# Dev_BRD_STM32F103C8T6.net
KiCad netlist of a schematic drawn in Altium Designer
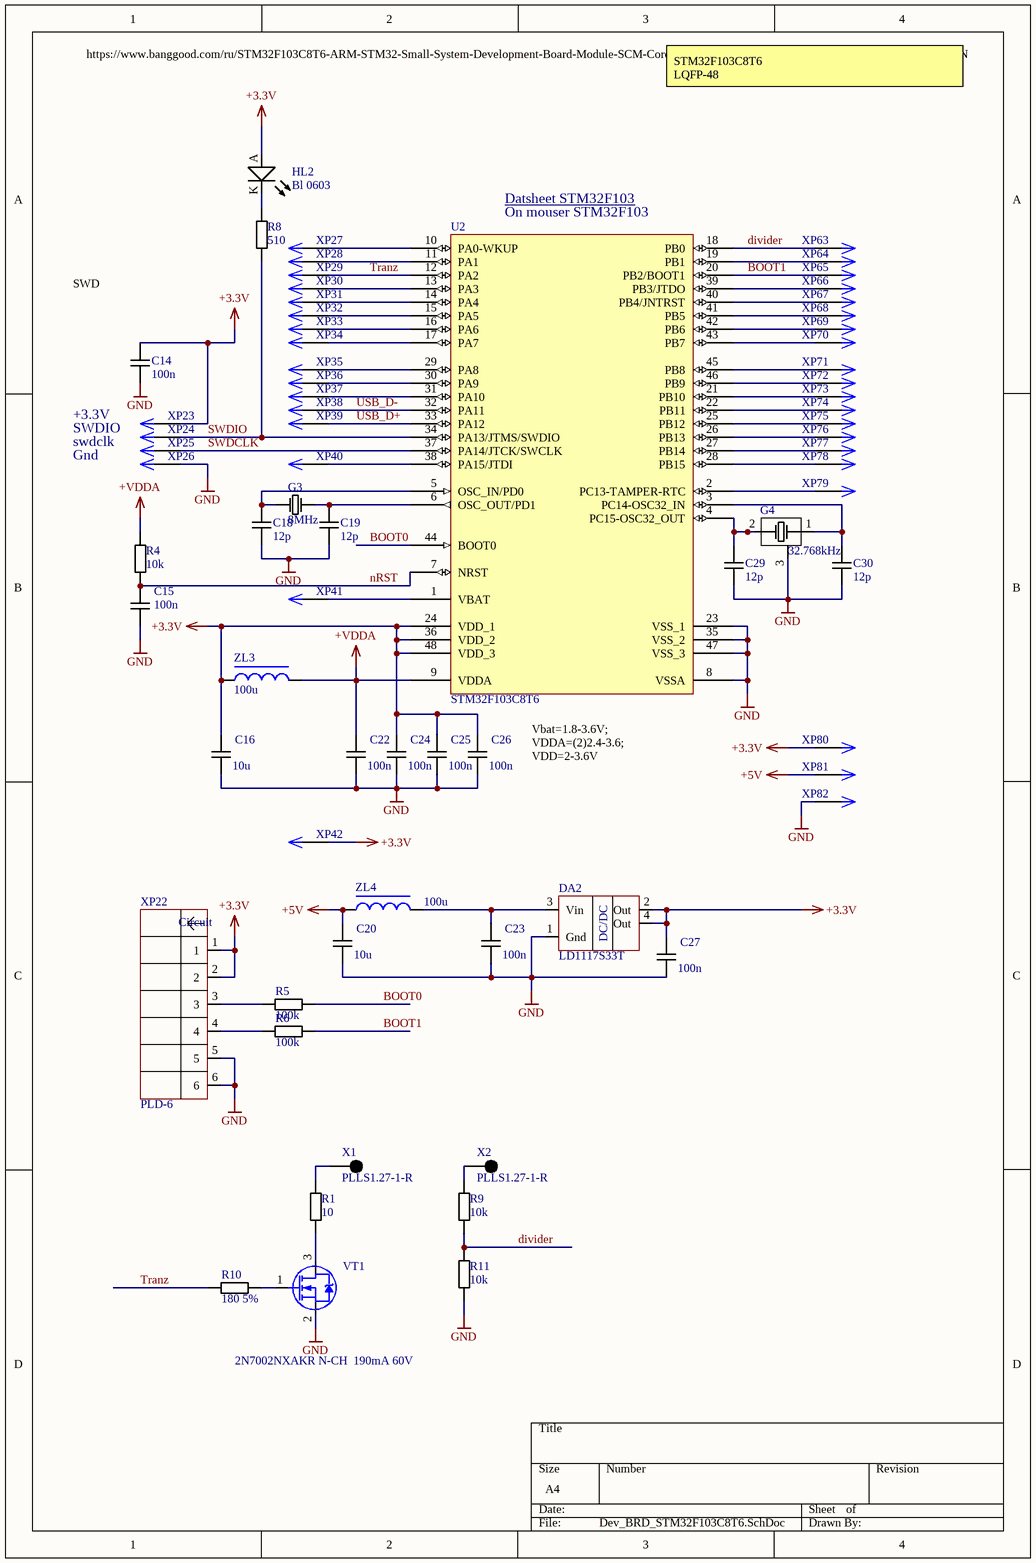
[diagram p0: Dev_BRD_STM32F103C8T6.SchDoc]

(export (version "E")
  (design (tool "Eeschema 10.0.6"))
  (components
    (comp (ref "C14")
      (value "100n")
      (footprint "CAPC1608(0603)N")
      (description "?")
      (fields (field (name "PART NUMBER") "CAPC1608(0603)"))
      (libsource (lib "SssAccesDatbase") (part "Cap"))
    )
    (comp (ref "C15")
      (value "100n")
      (footprint "CAPC1608(0603)N")
      (description "?")
      (fields (field (name "PART NUMBER") "CAPC1608(0603)"))
      (libsource (lib "SssAccesDatbase") (part "Cap"))
    )
    (comp (ref "C16")
      (value "10u")
      (footprint "CAPC1608(0603)N")
      (description "?")
      (fields (field (name "PART NUMBER") "CAPC1608(0603)"))
      (libsource (lib "SssAccesDatbase") (part "Cap"))
    )
    (comp (ref "C18")
      (value "12p")
      (footprint "CAPC1608(0603)N")
      (description "?")
      (fields (field (name "PART NUMBER") "CAPC1608(0603)"))
      (libsource (lib "SssAccesDatbase") (part "Cap"))
    )
    (comp (ref "C19")
      (value "12p")
      (footprint "CAPC1608(0603)N")
      (description "?")
      (fields (field (name "PART NUMBER") "CAPC1608(0603)"))
      (libsource (lib "SssAccesDatbase") (part "Cap"))
    )
    (comp (ref "C20")
      (value "10u")
      (footprint "CAPC1608(0603)N")
      (description "?")
      (fields (field (name "PART NUMBER") "CAPC1608(0603)"))
      (libsource (lib "SssAccesDatbase") (part "Cap"))
    )
    (comp (ref "C22")
      (value "100n")
      (footprint "CAPC1608(0603)N")
      (description "?")
      (fields (field (name "PART NUMBER") "CAPC1608(0603)"))
      (libsource (lib "SssAccesDatbase") (part "Cap"))
    )
    (comp (ref "C23")
      (value "100n")
      (footprint "CAPC1608(0603)N")
      (description "?")
      (fields (field (name "PART NUMBER") "CAPC1608(0603)"))
      (libsource (lib "SssAccesDatbase") (part "Cap"))
    )
    (comp (ref "C24")
      (value "100n")
      (footprint "CAPC1608(0603)N")
      (description "?")
      (fields (field (name "PART NUMBER") "CAPC1608(0603)"))
      (libsource (lib "SssAccesDatbase") (part "Cap"))
    )
    (comp (ref "C25")
      (value "100n")
      (footprint "CAPC1608(0603)N")
      (description "?")
      (fields (field (name "PART NUMBER") "CAPC1608(0603)"))
      (libsource (lib "SssAccesDatbase") (part "Cap"))
    )
    (comp (ref "C26")
      (value "100n")
      (footprint "CAPC1608(0603)N")
      (description "?")
      (fields (field (name "PART NUMBER") "CAPC1608(0603)"))
      (libsource (lib "SssAccesDatbase") (part "Cap"))
    )
    (comp (ref "C27")
      (value "100n")
      (footprint "CAPC1608(0603)N")
      (description "?")
      (fields (field (name "PART NUMBER") "CAPC1608(0603)"))
      (libsource (lib "SssAccesDatbase") (part "Cap"))
    )
    (comp (ref "C29")
      (value "12p")
      (footprint "CAPC1608(0603)N")
      (description "?")
      (fields (field (name "PART NUMBER") "CAPC1608(0603)"))
      (libsource (lib "SssAccesDatbase") (part "Cap"))
    )
    (comp (ref "C30")
      (value "12p")
      (footprint "CAPC1608(0603)N")
      (description "?")
      (fields (field (name "PART NUMBER") "CAPC1608(0603)"))
      (libsource (lib "SssAccesDatbase") (part "Cap"))
    )
    (comp (ref "DA2")
      (value "LD1117S33T")
      (footprint "SOT223_M")
      (description "LDO Voltage Regulators 3.3V 0.8A Positive")
      (fields (field (name "DIGI-KEY PART NUMBER") "?"))
      (libsource (lib "SssAccesDatbase") (part "LD1117S33T"))
    )
    (comp (ref "G3")
      (value "8MHz")
      (footprint "HC-49/S")
      (description "Crystal HC-49/S")
      (libsource (lib "SssAccesDatbase") (part "Crystal"))
    )
    (comp (ref "G4")
      (value "32.768kHz")
      (footprint "CRYSTAL_CMR309T")
      (description "Crystals 32.768KHz")
      (fields
        (field (name "PART NUMBER") "AB26T-32.768KHZ")
        (field (name "MOUSER PART NUMBER") "815-AB26T-32.768KHZ")
      )
      (libsource (lib "SssAccesDatbase") (part "Crystal 3 pin"))
    )
    (comp (ref "HL2")
      (value "Bl 0603")
      (footprint "LED-0603-BLUE")
      (description "LED BLUE DIFFUSED 0603 SMD")
      (fields
        (field (name "PART NUMBER") "150060BS55040")
        (field (name "DIGI-KEY PART NUMBER") "732-12013-1-ND")
      )
      (libsource (lib "SssAccesDatbase") (part "LED"))
    )
    (comp (ref "R1")
      (value "10")
      (footprint "REZKemet 0402")
      (description "RES SMD 0402 180 5% 100ppm")
      (fields
        (field (name "PART NUMBER") "RMCF0402JT180R")
        (field (name "DIGI-KEY PART NUMBER") "RMCF0402JT180RCT-ND")
      )
      (libsource (lib "SssAccesDatbase") (part "Resistor general"))
    )
    (comp (ref "R4")
      (value "10k")
      (footprint "RESC1608(0603)N")
      (fields (field (name "PART NUMBER") "RESC1608(0603)") (field (name "DIGI-KEY PART NUMBER") "???"))
      (libsource (lib "SssAccesDatbase") (part "Resistor general"))
    )
    (comp (ref "R5")
      (value "100k")
      (footprint "RESC1608(0603)N")
      (fields (field (name "PART NUMBER") "RESC1608(0603)") (field (name "DIGI-KEY PART NUMBER") "???"))
      (libsource (lib "") (part "Resistor general_1"))
    )
    (comp (ref "R6")
      (value "100k")
      (footprint "RESC1608(0603)N")
      (fields (field (name "PART NUMBER") "RESC1608(0603)") (field (name "DIGI-KEY PART NUMBER") "???"))
      (libsource (lib "") (part "Resistor general_1"))
    )
    (comp (ref "R8")
      (value "510")
      (footprint "RESC1608(0603)N")
      (fields (field (name "PART NUMBER") "RESC1608(0603)") (field (name "DIGI-KEY PART NUMBER") "???"))
      (libsource (lib "") (part "Resistor general_2"))
    )
    (comp (ref "R9")
      (value "10k")
      (footprint "RESC1608(0603)N")
      (fields (field (name "PART NUMBER") "RESC1608(0603)") (field (name "DIGI-KEY PART NUMBER") "???"))
      (libsource (lib "SssAccesDatbase") (part "Resistor general"))
    )
    (comp (ref "R10")
      (value "180 5%")
      (footprint "REZKemet 0402")
      (description "RES SMD 0402 180 5% 100ppm")
      (fields
        (field (name "PART NUMBER") "RMCF0402JT180R")
        (field (name "DIGI-KEY PART NUMBER") "RMCF0402JT180RCT-ND")
      )
      (libsource (lib "") (part "Resistor general_3"))
    )
    (comp (ref "R11")
      (value "10k")
      (footprint "RESC1608(0603)N")
      (fields (field (name "PART NUMBER") "RESC1608(0603)") (field (name "DIGI-KEY PART NUMBER") "???"))
      (libsource (lib "SssAccesDatbase") (part "Resistor general"))
    )
    (comp (ref "U2")
      (value "STM32F103C8T6")
      (footprint "LQFP48_L")
      (description "ARM Microcontrollers - MCU 32BIT Cortex M3 64KB 20KB RAM 2X12 ADC")
      (fields
        (field (name "MOUSER PART NUMBER") "511-STM32F103C8T6")
        (field (name "PUBLISHER") "Altium Limited")
      )
      (libsource (lib "SssAccesDatbase") (part "STM32F103C8T6"))
    )
    (comp (ref "VT1")
      (value "2N7002NXAKR N-CH  190mА 60V")
      (footprint "SOT23-3N")
      (description "N-Channel 60V 190mA (Ta), 300mA (Tc) 265mW (Ta), 1.33W (Tc) Surface Mount TO-236AB")
      (fields
        (field (name "PART NUMBER") "2N7002NXAKR")
        (field (name "DIGI-KEY PART NUMBER") "1727-8643-1-ND")
      )
      (libsource (lib "SssAccesDatbase") (part "N-CH_MOSFET_GSD"))
    )
    (comp (ref "X1")
      (value "PLLS1.27-1-R")
      (footprint "PLLS1.27-1-R")
      (libsource (lib "SssAccesDatbase") (part "X1_1"))
    )
    (comp (ref "X2")
      (value "PLLS1.27-1-R")
      (footprint "PLLS1.27-1-R")
      (libsource (lib "SssAccesDatbase") (part "X1_1"))
    )
    (comp (ref "XP22")
      (value "PLD-6")
      (footprint "PLD-6-3D")
      (libsource (lib "SssAccesDatbase") (part "XP-6"))
    )
    (comp (ref "XP23")
      (value "PLS-1")
      (footprint "PLS-1-3D")
      (description "CONN HEADER VERT 1POS")
      (fields
        (field (name "DIGI-KEY PART NUMBER") "S1011EC-01-ND")
        (field (name "MANUFACTURER PART NUMBER") "PRPC001SAAN-RC")
      )
      (libsource (lib "SssAccesDatbase") (part "XP-1_1"))
    )
    (comp (ref "XP24")
      (value "PLS-1")
      (footprint "PLS-1-3D")
      (description "CONN HEADER VERT 1POS")
      (fields
        (field (name "DIGI-KEY PART NUMBER") "S1011EC-01-ND")
        (field (name "MANUFACTURER PART NUMBER") "PRPC001SAAN-RC")
      )
      (libsource (lib "SssAccesDatbase") (part "XP-1_1"))
    )
    (comp (ref "XP25")
      (value "PLS-1")
      (footprint "PLS-1-3D")
      (description "CONN HEADER VERT 1POS")
      (fields
        (field (name "DIGI-KEY PART NUMBER") "S1011EC-01-ND")
        (field (name "MANUFACTURER PART NUMBER") "PRPC001SAAN-RC")
      )
      (libsource (lib "SssAccesDatbase") (part "XP-1_1"))
    )
    (comp (ref "XP26")
      (value "PLS-1")
      (footprint "PLS-1-3D")
      (description "CONN HEADER VERT 1POS")
      (fields
        (field (name "DIGI-KEY PART NUMBER") "S1011EC-01-ND")
        (field (name "MANUFACTURER PART NUMBER") "PRPC001SAAN-RC")
      )
      (libsource (lib "SssAccesDatbase") (part "XP-1_1"))
    )
    (comp (ref "XP27")
      (value "PLS-1")
      (footprint "PLS-1-3D")
      (description "CONN HEADER VERT 1POS")
      (fields
        (field (name "DIGI-KEY PART NUMBER") "S1011EC-01-ND")
        (field (name "MANUFACTURER PART NUMBER") "PRPC001SAAN-RC")
      )
      (libsource (lib "SssAccesDatbase") (part "XP-1_1"))
    )
    (comp (ref "XP28")
      (value "PLS-1")
      (footprint "PLS-1-3D")
      (description "CONN HEADER VERT 1POS")
      (fields
        (field (name "DIGI-KEY PART NUMBER") "S1011EC-01-ND")
        (field (name "MANUFACTURER PART NUMBER") "PRPC001SAAN-RC")
      )
      (libsource (lib "SssAccesDatbase") (part "XP-1_1"))
    )
    (comp (ref "XP29")
      (value "PLS-1")
      (footprint "PLS-1-3D")
      (description "CONN HEADER VERT 1POS")
      (fields
        (field (name "DIGI-KEY PART NUMBER") "S1011EC-01-ND")
        (field (name "MANUFACTURER PART NUMBER") "PRPC001SAAN-RC")
      )
      (libsource (lib "SssAccesDatbase") (part "XP-1_1"))
    )
    (comp (ref "XP30")
      (value "PLS-1")
      (footprint "PLS-1-3D")
      (description "CONN HEADER VERT 1POS")
      (fields
        (field (name "DIGI-KEY PART NUMBER") "S1011EC-01-ND")
        (field (name "MANUFACTURER PART NUMBER") "PRPC001SAAN-RC")
      )
      (libsource (lib "SssAccesDatbase") (part "XP-1_1"))
    )
    (comp (ref "XP31")
      (value "PLS-1")
      (footprint "PLS-1-3D")
      (description "CONN HEADER VERT 1POS")
      (fields
        (field (name "DIGI-KEY PART NUMBER") "S1011EC-01-ND")
        (field (name "MANUFACTURER PART NUMBER") "PRPC001SAAN-RC")
      )
      (libsource (lib "SssAccesDatbase") (part "XP-1_1"))
    )
    (comp (ref "XP32")
      (value "PLS-1")
      (footprint "PLS-1-3D")
      (description "CONN HEADER VERT 1POS")
      (fields
        (field (name "DIGI-KEY PART NUMBER") "S1011EC-01-ND")
        (field (name "MANUFACTURER PART NUMBER") "PRPC001SAAN-RC")
      )
      (libsource (lib "SssAccesDatbase") (part "XP-1_1"))
    )
    (comp (ref "XP33")
      (value "PLS-1")
      (footprint "PLS-1-3D")
      (description "CONN HEADER VERT 1POS")
      (fields
        (field (name "DIGI-KEY PART NUMBER") "S1011EC-01-ND")
        (field (name "MANUFACTURER PART NUMBER") "PRPC001SAAN-RC")
      )
      (libsource (lib "SssAccesDatbase") (part "XP-1_1"))
    )
    (comp (ref "XP34")
      (value "PLS-1")
      (footprint "PLS-1-3D")
      (description "CONN HEADER VERT 1POS")
      (fields
        (field (name "DIGI-KEY PART NUMBER") "S1011EC-01-ND")
        (field (name "MANUFACTURER PART NUMBER") "PRPC001SAAN-RC")
      )
      (libsource (lib "SssAccesDatbase") (part "XP-1_1"))
    )
    (comp (ref "XP35")
      (value "PLS-1")
      (footprint "PLS-1-3D")
      (description "CONN HEADER VERT 1POS")
      (fields
        (field (name "DIGI-KEY PART NUMBER") "S1011EC-01-ND")
        (field (name "MANUFACTURER PART NUMBER") "PRPC001SAAN-RC")
      )
      (libsource (lib "SssAccesDatbase") (part "XP-1_1"))
    )
    (comp (ref "XP36")
      (value "PLS-1")
      (footprint "PLS-1-3D")
      (description "CONN HEADER VERT 1POS")
      (fields
        (field (name "DIGI-KEY PART NUMBER") "S1011EC-01-ND")
        (field (name "MANUFACTURER PART NUMBER") "PRPC001SAAN-RC")
      )
      (libsource (lib "SssAccesDatbase") (part "XP-1_1"))
    )
    (comp (ref "XP37")
      (value "PLS-1")
      (footprint "PLS-1-3D")
      (description "CONN HEADER VERT 1POS")
      (fields
        (field (name "DIGI-KEY PART NUMBER") "S1011EC-01-ND")
        (field (name "MANUFACTURER PART NUMBER") "PRPC001SAAN-RC")
      )
      (libsource (lib "SssAccesDatbase") (part "XP-1_1"))
    )
    (comp (ref "XP38")
      (value "PLS-1")
      (footprint "PLS-1-3D")
      (description "CONN HEADER VERT 1POS")
      (fields
        (field (name "DIGI-KEY PART NUMBER") "S1011EC-01-ND")
        (field (name "MANUFACTURER PART NUMBER") "PRPC001SAAN-RC")
      )
      (libsource (lib "SssAccesDatbase") (part "XP-1_1"))
    )
    (comp (ref "XP39")
      (value "PLS-1")
      (footprint "PLS-1-3D")
      (description "CONN HEADER VERT 1POS")
      (fields
        (field (name "DIGI-KEY PART NUMBER") "S1011EC-01-ND")
        (field (name "MANUFACTURER PART NUMBER") "PRPC001SAAN-RC")
      )
      (libsource (lib "SssAccesDatbase") (part "XP-1_1"))
    )
    (comp (ref "XP40")
      (value "PLS-1")
      (footprint "PLS-1-3D")
      (description "CONN HEADER VERT 1POS")
      (fields
        (field (name "DIGI-KEY PART NUMBER") "S1011EC-01-ND")
        (field (name "MANUFACTURER PART NUMBER") "PRPC001SAAN-RC")
      )
      (libsource (lib "SssAccesDatbase") (part "XP-1_1"))
    )
    (comp (ref "XP41")
      (value "PLS-1")
      (footprint "PLS-1-3D")
      (description "CONN HEADER VERT 1POS")
      (fields
        (field (name "DIGI-KEY PART NUMBER") "S1011EC-01-ND")
        (field (name "MANUFACTURER PART NUMBER") "PRPC001SAAN-RC")
      )
      (libsource (lib "SssAccesDatbase") (part "XP-1_1"))
    )
    (comp (ref "XP42")
      (value "PLS-1")
      (footprint "PLS-1-3D")
      (description "CONN HEADER VERT 1POS")
      (fields
        (field (name "DIGI-KEY PART NUMBER") "S1011EC-01-ND")
        (field (name "MANUFACTURER PART NUMBER") "PRPC001SAAN-RC")
      )
      (libsource (lib "SssAccesDatbase") (part "XP-1_1"))
    )
    (comp (ref "XP63")
      (value "PLS-1")
      (footprint "PLS-1-3D")
      (description "CONN HEADER VERT 1POS")
      (fields
        (field (name "DIGI-KEY PART NUMBER") "S1011EC-01-ND")
        (field (name "MANUFACTURER PART NUMBER") "PRPC001SAAN-RC")
      )
      (libsource (lib "SssAccesDatbase") (part "XP-1_1"))
    )
    (comp (ref "XP64")
      (value "PLS-1")
      (footprint "PLS-1-3D")
      (description "CONN HEADER VERT 1POS")
      (fields
        (field (name "DIGI-KEY PART NUMBER") "S1011EC-01-ND")
        (field (name "MANUFACTURER PART NUMBER") "PRPC001SAAN-RC")
      )
      (libsource (lib "SssAccesDatbase") (part "XP-1_1"))
    )
    (comp (ref "XP65")
      (value "PLS-1")
      (footprint "PLS-1-3D")
      (description "CONN HEADER VERT 1POS")
      (fields
        (field (name "DIGI-KEY PART NUMBER") "S1011EC-01-ND")
        (field (name "MANUFACTURER PART NUMBER") "PRPC001SAAN-RC")
      )
      (libsource (lib "SssAccesDatbase") (part "XP-1_1"))
    )
    (comp (ref "XP66")
      (value "PLS-1")
      (footprint "PLS-1-3D")
      (description "CONN HEADER VERT 1POS")
      (fields
        (field (name "DIGI-KEY PART NUMBER") "S1011EC-01-ND")
        (field (name "MANUFACTURER PART NUMBER") "PRPC001SAAN-RC")
      )
      (libsource (lib "SssAccesDatbase") (part "XP-1_1"))
    )
    (comp (ref "XP67")
      (value "PLS-1")
      (footprint "PLS-1-3D")
      (description "CONN HEADER VERT 1POS")
      (fields
        (field (name "DIGI-KEY PART NUMBER") "S1011EC-01-ND")
        (field (name "MANUFACTURER PART NUMBER") "PRPC001SAAN-RC")
      )
      (libsource (lib "SssAccesDatbase") (part "XP-1_1"))
    )
    (comp (ref "XP68")
      (value "PLS-1")
      (footprint "PLS-1-3D")
      (description "CONN HEADER VERT 1POS")
      (fields
        (field (name "DIGI-KEY PART NUMBER") "S1011EC-01-ND")
        (field (name "MANUFACTURER PART NUMBER") "PRPC001SAAN-RC")
      )
      (libsource (lib "SssAccesDatbase") (part "XP-1_1"))
    )
    (comp (ref "XP69")
      (value "PLS-1")
      (footprint "PLS-1-3D")
      (description "CONN HEADER VERT 1POS")
      (fields
        (field (name "DIGI-KEY PART NUMBER") "S1011EC-01-ND")
        (field (name "MANUFACTURER PART NUMBER") "PRPC001SAAN-RC")
      )
      (libsource (lib "SssAccesDatbase") (part "XP-1_1"))
    )
    (comp (ref "XP70")
      (value "PLS-1")
      (footprint "PLS-1-3D")
      (description "CONN HEADER VERT 1POS")
      (fields
        (field (name "DIGI-KEY PART NUMBER") "S1011EC-01-ND")
        (field (name "MANUFACTURER PART NUMBER") "PRPC001SAAN-RC")
      )
      (libsource (lib "SssAccesDatbase") (part "XP-1_1"))
    )
    (comp (ref "XP71")
      (value "PLS-1")
      (footprint "PLS-1-3D")
      (description "CONN HEADER VERT 1POS")
      (fields
        (field (name "DIGI-KEY PART NUMBER") "S1011EC-01-ND")
        (field (name "MANUFACTURER PART NUMBER") "PRPC001SAAN-RC")
      )
      (libsource (lib "SssAccesDatbase") (part "XP-1_1"))
    )
    (comp (ref "XP72")
      (value "PLS-1")
      (footprint "PLS-1-3D")
      (description "CONN HEADER VERT 1POS")
      (fields
        (field (name "DIGI-KEY PART NUMBER") "S1011EC-01-ND")
        (field (name "MANUFACTURER PART NUMBER") "PRPC001SAAN-RC")
      )
      (libsource (lib "SssAccesDatbase") (part "XP-1_1"))
    )
    (comp (ref "XP73")
      (value "PLS-1")
      (footprint "PLS-1-3D")
      (description "CONN HEADER VERT 1POS")
      (fields
        (field (name "DIGI-KEY PART NUMBER") "S1011EC-01-ND")
        (field (name "MANUFACTURER PART NUMBER") "PRPC001SAAN-RC")
      )
      (libsource (lib "SssAccesDatbase") (part "XP-1_1"))
    )
    (comp (ref "XP74")
      (value "PLS-1")
      (footprint "PLS-1-3D")
      (description "CONN HEADER VERT 1POS")
      (fields
        (field (name "DIGI-KEY PART NUMBER") "S1011EC-01-ND")
        (field (name "MANUFACTURER PART NUMBER") "PRPC001SAAN-RC")
      )
      (libsource (lib "SssAccesDatbase") (part "XP-1_1"))
    )
    (comp (ref "XP75")
      (value "PLS-1")
      (footprint "PLS-1-3D")
      (description "CONN HEADER VERT 1POS")
      (fields
        (field (name "DIGI-KEY PART NUMBER") "S1011EC-01-ND")
        (field (name "MANUFACTURER PART NUMBER") "PRPC001SAAN-RC")
      )
      (libsource (lib "SssAccesDatbase") (part "XP-1_1"))
    )
    (comp (ref "XP76")
      (value "PLS-1")
      (footprint "PLS-1-3D")
      (description "CONN HEADER VERT 1POS")
      (fields
        (field (name "DIGI-KEY PART NUMBER") "S1011EC-01-ND")
        (field (name "MANUFACTURER PART NUMBER") "PRPC001SAAN-RC")
      )
      (libsource (lib "SssAccesDatbase") (part "XP-1_1"))
    )
    (comp (ref "XP77")
      (value "PLS-1")
      (footprint "PLS-1-3D")
      (description "CONN HEADER VERT 1POS")
      (fields
        (field (name "DIGI-KEY PART NUMBER") "S1011EC-01-ND")
        (field (name "MANUFACTURER PART NUMBER") "PRPC001SAAN-RC")
      )
      (libsource (lib "SssAccesDatbase") (part "XP-1_1"))
    )
    (comp (ref "XP78")
      (value "PLS-1")
      (footprint "PLS-1-3D")
      (description "CONN HEADER VERT 1POS")
      (fields
        (field (name "DIGI-KEY PART NUMBER") "S1011EC-01-ND")
        (field (name "MANUFACTURER PART NUMBER") "PRPC001SAAN-RC")
      )
      (libsource (lib "SssAccesDatbase") (part "XP-1_1"))
    )
    (comp (ref "XP79")
      (value "PLS-1")
      (footprint "PLS-1-3D")
      (description "CONN HEADER VERT 1POS")
      (fields
        (field (name "DIGI-KEY PART NUMBER") "S1011EC-01-ND")
        (field (name "MANUFACTURER PART NUMBER") "PRPC001SAAN-RC")
      )
      (libsource (lib "SssAccesDatbase") (part "XP-1_1"))
    )
    (comp (ref "XP80")
      (value "PLS-1")
      (footprint "PLS-1-3D")
      (description "CONN HEADER VERT 1POS")
      (fields
        (field (name "DIGI-KEY PART NUMBER") "S1011EC-01-ND")
        (field (name "MANUFACTURER PART NUMBER") "PRPC001SAAN-RC")
      )
      (libsource (lib "SssAccesDatbase") (part "XP-1_1"))
    )
    (comp (ref "XP81")
      (value "PLS-1")
      (footprint "PLS-1-3D")
      (description "CONN HEADER VERT 1POS")
      (fields
        (field (name "DIGI-KEY PART NUMBER") "S1011EC-01-ND")
        (field (name "MANUFACTURER PART NUMBER") "PRPC001SAAN-RC")
      )
      (libsource (lib "SssAccesDatbase") (part "XP-1_1"))
    )
    (comp (ref "XP82")
      (value "PLS-1")
      (footprint "PLS-1-3D")
      (description "CONN HEADER VERT 1POS")
      (fields
        (field (name "DIGI-KEY PART NUMBER") "S1011EC-01-ND")
        (field (name "MANUFACTURER PART NUMBER") "PRPC001SAAN-RC")
      )
      (libsource (lib "SssAccesDatbase") (part "XP-1_1"))
    )
    (comp (ref "ZL3")
      (value "100u")
      (footprint "INDC1608(0603)N")
      (description "ferite bead")
      (fields (field (name "PART NUMBER") "Ferite1608(0603)") (field (name "DIGI-KEY PART NUMBER") "???"))
      (libsource (lib "SssAccesDatbase") (part "ZL"))
    )
    (comp (ref "ZL4")
      (value "100u")
      (footprint "INDC1608(0603)N")
      (description "ferite bead")
      (fields (field (name "PART NUMBER") "Ferite1608(0603)") (field (name "DIGI-KEY PART NUMBER") "???"))
      (libsource (lib "SssAccesDatbase") (part "ZL"))
    )
  )
  (nets
    (net (code "1") (name "+3.3V") (class "Default")
      (node (ref "C14") (pin "1") (pinfunction "1_1") (pintype "passive"))
      (node (ref "C16") (pin "2") (pinfunction "2_2") (pintype "passive"))
      (node (ref "C24") (pin "2") (pinfunction "2_2") (pintype "passive"))
      (node (ref "C25") (pin "2") (pinfunction "2_2") (pintype "passive"))
      (node (ref "C26") (pin "2") (pinfunction "2_2") (pintype "passive"))
      (node (ref "C27") (pin "2") (pinfunction "2_2") (pintype "passive"))
      (node (ref "DA2") (pin "2") (pinfunction "Out_2") (pintype "passive"))
      (node (ref "DA2") (pin "4") (pinfunction "Out_4") (pintype "passive"))
      (node (ref "HL2") (pin "A") (pinfunction "A_A") (pintype "passive"))
      (node (ref "U2") (pin "24") (pinfunction "VDD_1_24") (pintype "power_in"))
      (node (ref "U2") (pin "36") (pinfunction "VDD_2_36") (pintype "power_in"))
      (node (ref "U2") (pin "48") (pinfunction "VDD_3_48") (pintype "power_in"))
      (node (ref "XP22") (pin "1") (pinfunction "1_1") (pintype "passive"))
      (node (ref "XP22") (pin "2") (pinfunction "2_2") (pintype "passive"))
      (node (ref "XP23") (pin "1") (pinfunction "1_1") (pintype "passive"))
      (node (ref "XP42") (pin "1") (pinfunction "1_1") (pintype "passive"))
      (node (ref "XP80") (pin "1") (pinfunction "1_1") (pintype "passive"))
      (node (ref "ZL3") (pin "1") (pinfunction "1_1") (pintype "passive"))
    )
    (net (code "2") (name "+5V") (class "Default")
      (node (ref "C20") (pin "2") (pinfunction "2_2") (pintype "passive"))
      (node (ref "XP81") (pin "1") (pinfunction "1_1") (pintype "passive"))
      (node (ref "ZL4") (pin "1") (pinfunction "1_1") (pintype "passive"))
    )
    (net (code "3") (name "+VDDA") (class "Default")
      (node (ref "C22") (pin "2") (pinfunction "2_2") (pintype "passive"))
      (node (ref "R4") (pin "2") (pinfunction "2_2") (pintype "passive"))
      (node (ref "U2") (pin "9") (pinfunction "VDDA_9") (pintype "power_in"))
      (node (ref "ZL3") (pin "2") (pinfunction "2_2") (pintype "passive"))
    )
    (net (code "4") (name "/BOOT0") (class "Default")
      (node (ref "R5") (pin "1") (pinfunction "1_1") (pintype "passive"))
      (node (ref "U2") (pin "44") (pinfunction "BOOT0_44") (pintype "input"))
    )
    (net (code "5") (name "/BOOT1") (class "Default")
      (node (ref "R6") (pin "1") (pinfunction "1_1") (pintype "passive"))
      (node (ref "U2") (pin "20") (pinfunction "PB2/BOOT1_20") (pintype "bidirectional"))
      (node (ref "XP65") (pin "1") (pinfunction "1_1") (pintype "passive"))
    )
    (net (code "6") (name "/SWDCLK") (class "Default")
      (node (ref "U2") (pin "37") (pinfunction "PA14/JTCK/SWCLK_37") (pintype "bidirectional"))
      (node (ref "XP25") (pin "1") (pinfunction "1_1") (pintype "passive"))
    )
    (net (code "7") (name "/SWDIO") (class "Default")
      (node (ref "R8") (pin "2") (pinfunction "2_2") (pintype "passive"))
      (node (ref "U2") (pin "34") (pinfunction "PA13/JTMS/SWDIO_34") (pintype "bidirectional"))
      (node (ref "XP24") (pin "1") (pinfunction "1_1") (pintype "passive"))
    )
    (net (code "8") (name "/Tranz") (class "Default")
      (node (ref "R10") (pin "1") (pinfunction "1_1") (pintype "passive"))
      (node (ref "U2") (pin "12") (pinfunction "PA2_12") (pintype "bidirectional"))
      (node (ref "XP29") (pin "1") (pinfunction "1_1") (pintype "passive"))
    )
    (net (code "9") (name "/USB_D+") (class "Default")
      (node (ref "U2") (pin "33") (pinfunction "PA12_33") (pintype "bidirectional"))
      (node (ref "XP39") (pin "1") (pinfunction "1_1") (pintype "passive"))
    )
    (net (code "10") (name "/USB_D-") (class "Default")
      (node (ref "U2") (pin "32") (pinfunction "PA11_32") (pintype "bidirectional"))
      (node (ref "XP38") (pin "1") (pinfunction "1_1") (pintype "passive"))
    )
    (net (code "11") (name "/divider") (class "Default")
      (node (ref "R11") (pin "2") (pinfunction "2_2") (pintype "passive"))
      (node (ref "R9") (pin "1") (pinfunction "1_1") (pintype "passive"))
      (node (ref "U2") (pin "18") (pinfunction "PB0_18") (pintype "bidirectional"))
      (node (ref "XP63") (pin "1") (pinfunction "1_1") (pintype "passive"))
    )
    (net (code "12") (name "/nRST") (class "Default")
      (node (ref "C15") (pin "2") (pinfunction "2_2") (pintype "passive"))
      (node (ref "R4") (pin "1") (pinfunction "1_1") (pintype "passive"))
      (node (ref "U2") (pin "7") (pinfunction "NRST_7") (pintype "bidirectional"))
    )
    (net (code "13") (name "GND") (class "Default")
      (node (ref "C14") (pin "2") (pinfunction "2_2") (pintype "passive"))
      (node (ref "C15") (pin "1") (pinfunction "1_1") (pintype "passive"))
      (node (ref "C16") (pin "1") (pinfunction "1_1") (pintype "passive"))
      (node (ref "C18") (pin "1") (pinfunction "1_1") (pintype "passive"))
      (node (ref "C19") (pin "1") (pinfunction "1_1") (pintype "passive"))
      (node (ref "C20") (pin "1") (pinfunction "1_1") (pintype "passive"))
      (node (ref "C22") (pin "1") (pinfunction "1_1") (pintype "passive"))
      (node (ref "C23") (pin "1") (pinfunction "1_1") (pintype "passive"))
      (node (ref "C24") (pin "1") (pinfunction "1_1") (pintype "passive"))
      (node (ref "C25") (pin "1") (pinfunction "1_1") (pintype "passive"))
      (node (ref "C26") (pin "1") (pinfunction "1_1") (pintype "passive"))
      (node (ref "C27") (pin "1") (pinfunction "1_1") (pintype "passive"))
      (node (ref "C29") (pin "1") (pinfunction "1_1") (pintype "passive"))
      (node (ref "C30") (pin "1") (pinfunction "1_1") (pintype "passive"))
      (node (ref "DA2") (pin "1") (pinfunction "Gnd_1") (pintype "passive"))
      (node (ref "G4") (pin "3") (pinfunction "3_3") (pintype "passive"))
      (node (ref "R11") (pin "1") (pinfunction "1_1") (pintype "passive"))
      (node (ref "U2") (pin "23") (pinfunction "VSS_1_23") (pintype "power_in"))
      (node (ref "U2") (pin "35") (pinfunction "VSS_2_35") (pintype "power_in"))
      (node (ref "U2") (pin "47") (pinfunction "VSS_3_47") (pintype "power_in"))
      (node (ref "U2") (pin "8") (pinfunction "VSSA_8") (pintype "power_in"))
      (node (ref "VT1") (pin "2") (pinfunction "S_2") (pintype "passive"))
      (node (ref "XP22") (pin "5") (pinfunction "5_5") (pintype "passive"))
      (node (ref "XP22") (pin "6") (pinfunction "6_6") (pintype "passive"))
      (node (ref "XP26") (pin "1") (pinfunction "1_1") (pintype "passive"))
      (node (ref "XP82") (pin "1") (pinfunction "1_1") (pintype "passive"))
    )
    (net (code "14") (name "Net-(DA2-Vin)") (class "Default")
      (node (ref "C23") (pin "2") (pinfunction "2_2") (pintype "passive"))
      (node (ref "DA2") (pin "3") (pinfunction "Vin_3") (pintype "passive"))
      (node (ref "ZL4") (pin "2") (pinfunction "2_2") (pintype "passive"))
    )
    (net (code "15") (name "Net-(HL2-PadK)") (class "Default")
      (node (ref "HL2") (pin "K") (pinfunction "K_K") (pintype "passive"))
      (node (ref "R8") (pin "1") (pinfunction "1_1") (pintype "passive"))
    )
    (net (code "16") (name "Net-(R1-Pad2)") (class "Default")
      (node (ref "R1") (pin "2") (pinfunction "2_2") (pintype "passive"))
      (node (ref "X1") (pin "1") (pinfunction "1_1") (pintype "passive"))
    )
    (net (code "17") (name "Net-(R5-Pad2)") (class "Default")
      (node (ref "R5") (pin "2") (pinfunction "2_2") (pintype "passive"))
      (node (ref "XP22") (pin "3") (pinfunction "3_3") (pintype "passive"))
    )
    (net (code "18") (name "Net-(R6-Pad2)") (class "Default")
      (node (ref "R6") (pin "2") (pinfunction "2_2") (pintype "passive"))
      (node (ref "XP22") (pin "4") (pinfunction "4_4") (pintype "passive"))
    )
    (net (code "19") (name "Net-(R9-Pad2)") (class "Default")
      (node (ref "R9") (pin "2") (pinfunction "2_2") (pintype "passive"))
      (node (ref "X2") (pin "1") (pinfunction "1_1") (pintype "passive"))
    )
    (net (code "20") (name "Net-(U2-OSC_IN{slash}PD0)") (class "Default")
      (node (ref "C18") (pin "2") (pinfunction "2_2") (pintype "passive"))
      (node (ref "G3") (pin "1") (pinfunction "1_1") (pintype "passive"))
      (node (ref "U2") (pin "5") (pinfunction "OSC_IN/PD0_5") (pintype "input"))
    )
    (net (code "21") (name "Net-(U2-OSC_OUT{slash}PD1)") (class "Default")
      (node (ref "C19") (pin "2") (pinfunction "2_2") (pintype "passive"))
      (node (ref "G3") (pin "2") (pinfunction "2_2") (pintype "passive"))
      (node (ref "U2") (pin "6") (pinfunction "OSC_OUT/PD1_6") (pintype "output"))
    )
    (net (code "22") (name "Net-(U2-PA0-WKUP)") (class "Default")
      (node (ref "U2") (pin "10") (pinfunction "PA0-WKUP_10") (pintype "bidirectional"))
      (node (ref "XP27") (pin "1") (pinfunction "1_1") (pintype "passive"))
    )
    (net (code "23") (name "Net-(U2-PA1)") (class "Default")
      (node (ref "U2") (pin "11") (pinfunction "PA1_11") (pintype "bidirectional"))
      (node (ref "XP28") (pin "1") (pinfunction "1_1") (pintype "passive"))
    )
    (net (code "24") (name "Net-(U2-PA3)") (class "Default")
      (node (ref "U2") (pin "13") (pinfunction "PA3_13") (pintype "bidirectional"))
      (node (ref "XP30") (pin "1") (pinfunction "1_1") (pintype "passive"))
    )
    (net (code "25") (name "Net-(U2-PA4)") (class "Default")
      (node (ref "U2") (pin "14") (pinfunction "PA4_14") (pintype "bidirectional"))
      (node (ref "XP31") (pin "1") (pinfunction "1_1") (pintype "passive"))
    )
    (net (code "26") (name "Net-(U2-PA5)") (class "Default")
      (node (ref "U2") (pin "15") (pinfunction "PA5_15") (pintype "bidirectional"))
      (node (ref "XP32") (pin "1") (pinfunction "1_1") (pintype "passive"))
    )
    (net (code "27") (name "Net-(U2-PA6)") (class "Default")
      (node (ref "U2") (pin "16") (pinfunction "PA6_16") (pintype "bidirectional"))
      (node (ref "XP33") (pin "1") (pinfunction "1_1") (pintype "passive"))
    )
    (net (code "28") (name "Net-(U2-PA7)") (class "Default")
      (node (ref "U2") (pin "17") (pinfunction "PA7_17") (pintype "bidirectional"))
      (node (ref "XP34") (pin "1") (pinfunction "1_1") (pintype "passive"))
    )
    (net (code "29") (name "Net-(U2-PA8)") (class "Default")
      (node (ref "U2") (pin "29") (pinfunction "PA8_29") (pintype "bidirectional"))
      (node (ref "XP35") (pin "1") (pinfunction "1_1") (pintype "passive"))
    )
    (net (code "30") (name "Net-(U2-PA9)") (class "Default")
      (node (ref "U2") (pin "30") (pinfunction "PA9_30") (pintype "bidirectional"))
      (node (ref "XP36") (pin "1") (pinfunction "1_1") (pintype "passive"))
    )
    (net (code "31") (name "Net-(U2-PA10)") (class "Default")
      (node (ref "U2") (pin "31") (pinfunction "PA10_31") (pintype "bidirectional"))
      (node (ref "XP37") (pin "1") (pinfunction "1_1") (pintype "passive"))
    )
    (net (code "32") (name "Net-(U2-PA15{slash}JTDI)") (class "Default")
      (node (ref "U2") (pin "38") (pinfunction "PA15/JTDI_38") (pintype "bidirectional"))
      (node (ref "XP40") (pin "1") (pinfunction "1_1") (pintype "passive"))
    )
    (net (code "33") (name "Net-(U2-PB1)") (class "Default")
      (node (ref "U2") (pin "19") (pinfunction "PB1_19") (pintype "bidirectional"))
      (node (ref "XP64") (pin "1") (pinfunction "1_1") (pintype "passive"))
    )
    (net (code "34") (name "Net-(U2-PB3{slash}JTDO)") (class "Default")
      (node (ref "U2") (pin "39") (pinfunction "PB3/JTDO_39") (pintype "bidirectional"))
      (node (ref "XP66") (pin "1") (pinfunction "1_1") (pintype "passive"))
    )
    (net (code "35") (name "Net-(U2-PB4{slash}JNTRST)") (class "Default")
      (node (ref "U2") (pin "40") (pinfunction "PB4/JNTRST_40") (pintype "bidirectional"))
      (node (ref "XP67") (pin "1") (pinfunction "1_1") (pintype "passive"))
    )
    (net (code "36") (name "Net-(U2-PB5)") (class "Default")
      (node (ref "U2") (pin "41") (pinfunction "PB5_41") (pintype "bidirectional"))
      (node (ref "XP68") (pin "1") (pinfunction "1_1") (pintype "passive"))
    )
    (net (code "37") (name "Net-(U2-PB6)") (class "Default")
      (node (ref "U2") (pin "42") (pinfunction "PB6_42") (pintype "bidirectional"))
      (node (ref "XP69") (pin "1") (pinfunction "1_1") (pintype "passive"))
    )
    (net (code "38") (name "Net-(U2-PB7)") (class "Default")
      (node (ref "U2") (pin "43") (pinfunction "PB7_43") (pintype "bidirectional"))
      (node (ref "XP70") (pin "1") (pinfunction "1_1") (pintype "passive"))
    )
    (net (code "39") (name "Net-(U2-PB8)") (class "Default")
      (node (ref "U2") (pin "45") (pinfunction "PB8_45") (pintype "bidirectional"))
      (node (ref "XP71") (pin "1") (pinfunction "1_1") (pintype "passive"))
    )
    (net (code "40") (name "Net-(U2-PB9)") (class "Default")
      (node (ref "U2") (pin "46") (pinfunction "PB9_46") (pintype "bidirectional"))
      (node (ref "XP72") (pin "1") (pinfunction "1_1") (pintype "passive"))
    )
    (net (code "41") (name "Net-(U2-PB10)") (class "Default")
      (node (ref "U2") (pin "21") (pinfunction "PB10_21") (pintype "bidirectional"))
      (node (ref "XP73") (pin "1") (pinfunction "1_1") (pintype "passive"))
    )
    (net (code "42") (name "Net-(U2-PB11)") (class "Default")
      (node (ref "U2") (pin "22") (pinfunction "PB11_22") (pintype "bidirectional"))
      (node (ref "XP74") (pin "1") (pinfunction "1_1") (pintype "passive"))
    )
    (net (code "43") (name "Net-(U2-PB12)") (class "Default")
      (node (ref "U2") (pin "25") (pinfunction "PB12_25") (pintype "bidirectional"))
      (node (ref "XP75") (pin "1") (pinfunction "1_1") (pintype "passive"))
    )
    (net (code "44") (name "Net-(U2-PB13)") (class "Default")
      (node (ref "U2") (pin "26") (pinfunction "PB13_26") (pintype "bidirectional"))
      (node (ref "XP76") (pin "1") (pinfunction "1_1") (pintype "passive"))
    )
    (net (code "45") (name "Net-(U2-PB14)") (class "Default")
      (node (ref "U2") (pin "27") (pinfunction "PB14_27") (pintype "bidirectional"))
      (node (ref "XP77") (pin "1") (pinfunction "1_1") (pintype "passive"))
    )
    (net (code "46") (name "Net-(U2-PB15)") (class "Default")
      (node (ref "U2") (pin "28") (pinfunction "PB15_28") (pintype "bidirectional"))
      (node (ref "XP78") (pin "1") (pinfunction "1_1") (pintype "passive"))
    )
    (net (code "47") (name "Net-(U2-PC13-TAMPER-RTC)") (class "Default")
      (node (ref "U2") (pin "2") (pinfunction "PC13-TAMPER-RTC_2") (pintype "bidirectional"))
      (node (ref "XP79") (pin "1") (pinfunction "1_1") (pintype "passive"))
    )
    (net (code "48") (name "Net-(U2-PC14-OSC32_IN)") (class "Default")
      (node (ref "C30") (pin "2") (pinfunction "2_2") (pintype "passive"))
      (node (ref "G4") (pin "1") (pinfunction "1_1") (pintype "passive"))
      (node (ref "U2") (pin "3") (pinfunction "PC14-OSC32_IN_3") (pintype "bidirectional"))
    )
    (net (code "49") (name "Net-(U2-PC15-OSC32_OUT)") (class "Default")
      (node (ref "C29") (pin "2") (pinfunction "2_2") (pintype "passive"))
      (node (ref "G4") (pin "2") (pinfunction "2_2") (pintype "passive"))
      (node (ref "U2") (pin "4") (pinfunction "PC15-OSC32_OUT_4") (pintype "bidirectional"))
    )
    (net (code "50") (name "Net-(U2-VBAT)") (class "Default")
      (node (ref "U2") (pin "1") (pinfunction "VBAT_1") (pintype "power_in"))
      (node (ref "XP41") (pin "1") (pinfunction "1_1") (pintype "passive"))
    )
    (net (code "51") (name "Net-(VT1-D)") (class "Default")
      (node (ref "R1") (pin "1") (pinfunction "1_1") (pintype "passive"))
      (node (ref "VT1") (pin "3") (pinfunction "D_3") (pintype "passive"))
    )
    (net (code "52") (name "Net-(VT1-G)") (class "Default")
      (node (ref "R10") (pin "2") (pinfunction "2_2") (pintype "passive"))
      (node (ref "VT1") (pin "1") (pinfunction "G_1") (pintype "passive"))
    )
  )
)
